# controller.net
KiCad netlist of a schematic drawn in EAGLE
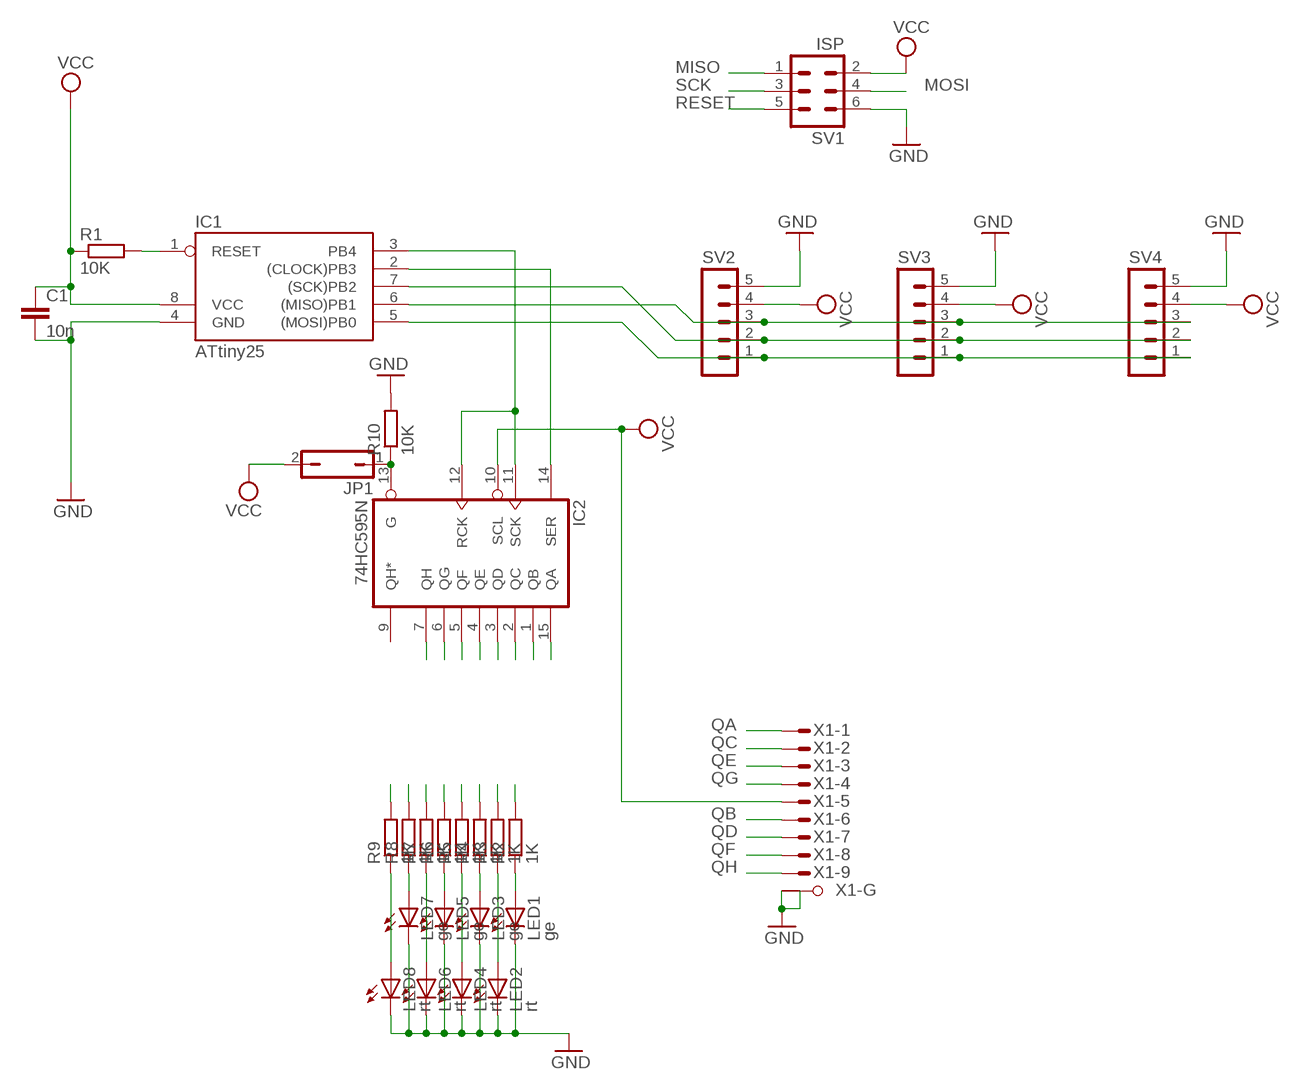
[diagram p0: schematic, sheet 1]

(export (version "E")
  (design (tool "Eeschema 10.0.6"))
  (components
    (comp (ref "C1")
      (value "10n")
      (footprint "eagle-import:C025-024X044")
      (libsource (lib "eagle-import") (part "C-EU025-024X044"))
    )
    (comp (ref "IC1")
      (value "ATtiny25")
      (footprint "eagle-import:DIL08")
      (libsource (lib "eagle-import") (part "AT902343PS"))
    )
    (comp (ref "IC2")
      (value "74HC595N")
      (footprint "eagle-import:DIL16")
      (libsource (lib "eagle-import") (part "74595NHC"))
    )
    (comp (ref "JP1")
      (value "JP1Q")
      (footprint "eagle-import:JP1")
      (libsource (lib "eagle-import") (part "JP1Q"))
    )
    (comp (ref "LED1")
      (value "ge")
      (footprint "eagle-import:LED5MM")
      (libsource (lib "eagle-import") (part "LED5MM"))
    )
    (comp (ref "LED2")
      (value "rt")
      (footprint "eagle-import:LED5MM")
      (libsource (lib "eagle-import") (part "LED5MM"))
    )
    (comp (ref "LED3")
      (value "ge")
      (footprint "eagle-import:LED5MM")
      (libsource (lib "eagle-import") (part "LED5MM"))
    )
    (comp (ref "LED4")
      (value "rt")
      (footprint "eagle-import:LED5MM")
      (libsource (lib "eagle-import") (part "LED5MM"))
    )
    (comp (ref "LED5")
      (value "ge")
      (footprint "eagle-import:LED5MM")
      (libsource (lib "eagle-import") (part "LED5MM"))
    )
    (comp (ref "LED6")
      (value "rt")
      (footprint "eagle-import:LED5MM")
      (libsource (lib "eagle-import") (part "LED5MM"))
    )
    (comp (ref "LED7")
      (value "ge")
      (footprint "eagle-import:LED5MM")
      (libsource (lib "eagle-import") (part "LED5MM"))
    )
    (comp (ref "LED8")
      (value "rt")
      (footprint "eagle-import:LED5MM")
      (libsource (lib "eagle-import") (part "LED5MM"))
    )
    (comp (ref "R1")
      (value "10K")
      (footprint "eagle-import:0207_7")
      (libsource (lib "eagle-import") (part "R-EU_0207/7"))
    )
    (comp (ref "R2")
      (value "1K")
      (footprint "eagle-import:0309_12")
      (libsource (lib "eagle-import") (part "R-EU_0309/12"))
    )
    (comp (ref "R3")
      (value "1K")
      (footprint "eagle-import:0309_12")
      (libsource (lib "eagle-import") (part "R-EU_0309/12"))
    )
    (comp (ref "R4")
      (value "1K")
      (footprint "eagle-import:0309_12")
      (libsource (lib "eagle-import") (part "R-EU_0309/12"))
    )
    (comp (ref "R5")
      (value "1K")
      (footprint "eagle-import:0309_12")
      (libsource (lib "eagle-import") (part "R-EU_0309/12"))
    )
    (comp (ref "R6")
      (value "1K")
      (footprint "eagle-import:0309_12")
      (libsource (lib "eagle-import") (part "R-EU_0309/12"))
    )
    (comp (ref "R7")
      (value "1K")
      (footprint "eagle-import:0309_12")
      (libsource (lib "eagle-import") (part "R-EU_0309/12"))
    )
    (comp (ref "R8")
      (value "1K")
      (footprint "eagle-import:0309_12")
      (libsource (lib "eagle-import") (part "R-EU_0309/12"))
    )
    (comp (ref "R9")
      (value "1K")
      (footprint "eagle-import:0309_12")
      (libsource (lib "eagle-import") (part "R-EU_0309/12"))
    )
    (comp (ref "R10")
      (value "10K")
      (footprint "eagle-import:0207_7")
      (libsource (lib "eagle-import") (part "R-EU_0207/7"))
    )
    (comp (ref "SV1")
      (value "ISP")
      (footprint "eagle-import:MA03-2")
      (libsource (lib "eagle-import") (part "MA03-2"))
    )
    (comp (ref "SV2")
      (value "MA05-1")
      (footprint "eagle-import:MA05-1")
      (libsource (lib "eagle-import") (part "MA05-1"))
    )
    (comp (ref "SV3")
      (value "MA05-1")
      (footprint "eagle-import:MA05-1")
      (libsource (lib "eagle-import") (part "MA05-1"))
    )
    (comp (ref "SV4")
      (value "MA05-1")
      (footprint "eagle-import:MA05-1")
      (libsource (lib "eagle-import") (part "MA05-1"))
    )
    (comp (ref "X1")
      (value "M09HPS")
      (footprint "eagle-import:M09HP")
      (libsource (lib "eagle-import") (part "M09HPS"))
    )
  )
  (nets
    (net (code "1") (name "/MISO") (class "Default")
      (node (ref "IC1") (pin "6") (pinfunction "(MISO)PB1_6") (pintype "bidirectional"))
      (node (ref "SV1") (pin "1") (pinfunction "1_1") (pintype "passive"))
      (node (ref "SV2") (pin "3") (pinfunction "3_3") (pintype "passive"))
      (node (ref "SV3") (pin "3") (pinfunction "3_3") (pintype "passive"))
      (node (ref "SV4") (pin "3") (pinfunction "3_3") (pintype "passive"))
    )
    (net (code "2") (name "/MOSI") (class "Default")
      (node (ref "IC1") (pin "5") (pinfunction "(MOSI)PB0_5") (pintype "bidirectional"))
      (node (ref "SV1") (pin "4") (pinfunction "4_4") (pintype "passive"))
      (node (ref "SV2") (pin "1") (pinfunction "1_1") (pintype "passive"))
      (node (ref "SV3") (pin "1") (pinfunction "1_1") (pintype "passive"))
      (node (ref "SV4") (pin "1") (pinfunction "1_1") (pintype "passive"))
    )
    (net (code "3") (name "/QA") (class "Default")
      (node (ref "IC2") (pin "15") (pinfunction "QA_15") (pintype "tri_state"))
      (node (ref "R2") (pin "2") (pinfunction "2_2") (pintype "passive"))
      (node (ref "X1") (pin "1") (pinfunction "M_1") (pintype "passive"))
    )
    (net (code "4") (name "/QB") (class "Default")
      (node (ref "IC2") (pin "1") (pinfunction "QB_1") (pintype "tri_state"))
      (node (ref "R6") (pin "2") (pinfunction "2_2") (pintype "passive"))
      (node (ref "X1") (pin "6") (pinfunction "M_6") (pintype "passive"))
    )
    (net (code "5") (name "/QC") (class "Default")
      (node (ref "IC2") (pin "2") (pinfunction "QC_2") (pintype "tri_state"))
      (node (ref "R3") (pin "2") (pinfunction "2_2") (pintype "passive"))
      (node (ref "X1") (pin "2") (pinfunction "M_2") (pintype "passive"))
    )
    (net (code "6") (name "/QD") (class "Default")
      (node (ref "IC2") (pin "3") (pinfunction "QD_3") (pintype "tri_state"))
      (node (ref "R7") (pin "2") (pinfunction "2_2") (pintype "passive"))
      (node (ref "X1") (pin "7") (pinfunction "M_7") (pintype "passive"))
    )
    (net (code "7") (name "/QE") (class "Default")
      (node (ref "IC2") (pin "4") (pinfunction "QE_4") (pintype "tri_state"))
      (node (ref "R4") (pin "2") (pinfunction "2_2") (pintype "passive"))
      (node (ref "X1") (pin "3") (pinfunction "M_3") (pintype "passive"))
    )
    (net (code "8") (name "/QF") (class "Default")
      (node (ref "IC2") (pin "5") (pinfunction "QF_5") (pintype "tri_state"))
      (node (ref "R8") (pin "2") (pinfunction "2_2") (pintype "passive"))
      (node (ref "X1") (pin "8") (pinfunction "M_8") (pintype "passive"))
    )
    (net (code "9") (name "/QG") (class "Default")
      (node (ref "IC2") (pin "6") (pinfunction "QG_6") (pintype "tri_state"))
      (node (ref "R5") (pin "2") (pinfunction "2_2") (pintype "passive"))
      (node (ref "X1") (pin "4") (pinfunction "M_4") (pintype "passive"))
    )
    (net (code "10") (name "/QH") (class "Default")
      (node (ref "IC2") (pin "7") (pinfunction "QH_7") (pintype "tri_state"))
      (node (ref "R9") (pin "2") (pinfunction "2_2") (pintype "passive"))
      (node (ref "X1") (pin "9") (pinfunction "M_9") (pintype "passive"))
    )
    (net (code "11") (name "/RESET") (class "Default")
      (node (ref "IC1") (pin "1") (pinfunction "RESET_1") (pintype "input"))
      (node (ref "R1") (pin "2") (pinfunction "2_2") (pintype "passive"))
      (node (ref "SV1") (pin "5") (pinfunction "5_5") (pintype "passive"))
    )
    (net (code "12") (name "/SCK") (class "Default")
      (node (ref "IC1") (pin "7") (pinfunction "(SCK)PB2_7") (pintype "bidirectional"))
      (node (ref "SV1") (pin "3") (pinfunction "3_3") (pintype "passive"))
      (node (ref "SV2") (pin "2") (pinfunction "2_2") (pintype "passive"))
      (node (ref "SV3") (pin "2") (pinfunction "2_2") (pintype "passive"))
      (node (ref "SV4") (pin "2") (pinfunction "2_2") (pintype "passive"))
    )
    (net (code "13") (name "GND") (class "Default")
      (node (ref "C1") (pin "2") (pinfunction "2_2") (pintype "passive"))
      (node (ref "IC1") (pin "4") (pinfunction "GND_4") (pintype "power_in"))
      (node (ref "LED1") (pin "K") (pinfunction "C_K") (pintype "passive"))
      (node (ref "LED2") (pin "K") (pinfunction "C_K") (pintype "passive"))
      (node (ref "LED3") (pin "K") (pinfunction "C_K") (pintype "passive"))
      (node (ref "LED4") (pin "K") (pinfunction "C_K") (pintype "passive"))
      (node (ref "LED5") (pin "K") (pinfunction "C_K") (pintype "passive"))
      (node (ref "LED6") (pin "K") (pinfunction "C_K") (pintype "passive"))
      (node (ref "LED7") (pin "K") (pinfunction "C_K") (pintype "passive"))
      (node (ref "LED8") (pin "K") (pinfunction "C_K") (pintype "passive"))
      (node (ref "R10") (pin "2") (pinfunction "2_2") (pintype "passive"))
      (node (ref "SV1") (pin "6") (pinfunction "6_6") (pintype "passive"))
      (node (ref "SV2") (pin "5") (pinfunction "5_5") (pintype "passive"))
      (node (ref "SV3") (pin "5") (pinfunction "5_5") (pintype "passive"))
      (node (ref "SV4") (pin "5") (pinfunction "5_5") (pintype "passive"))
      (node (ref "X1") (pin "G1") (pinfunction "G1_G1") (pintype "passive"))
      (node (ref "X1") (pin "G2") (pinfunction "G2_G2") (pintype "passive"))
    )
    (net (code "14") (name "Net-(IC1-(CLOCK)PB3)") (class "Default")
      (node (ref "IC1") (pin "2") (pinfunction "(CLOCK)PB3_2") (pintype "bidirectional"))
      (node (ref "IC2") (pin "14") (pinfunction "SER_14") (pintype "input"))
    )
    (net (code "15") (name "Net-(IC1-PB4)") (class "Default")
      (node (ref "IC1") (pin "3") (pinfunction "PB4_3") (pintype "bidirectional"))
      (node (ref "IC2") (pin "11") (pinfunction "SCK_11") (pintype "input"))
      (node (ref "IC2") (pin "12") (pinfunction "RCK_12") (pintype "input"))
    )
    (net (code "16") (name "Net-(IC2A-G)") (class "Default")
      (node (ref "IC2") (pin "13") (pinfunction "G_13") (pintype "input"))
      (node (ref "JP1") (pin "1") (pinfunction "1_1") (pintype "passive"))
      (node (ref "R10") (pin "1") (pinfunction "1_1") (pintype "passive"))
    )
    (net (code "17") (name "Net-(LED1-PadA)") (class "Default")
      (node (ref "LED1") (pin "A") (pinfunction "A_A") (pintype "passive"))
      (node (ref "R2") (pin "1") (pinfunction "1_1") (pintype "passive"))
    )
    (net (code "18") (name "Net-(LED2-PadA)") (class "Default")
      (node (ref "LED2") (pin "A") (pinfunction "A_A") (pintype "passive"))
      (node (ref "R3") (pin "1") (pinfunction "1_1") (pintype "passive"))
    )
    (net (code "19") (name "Net-(LED3-PadA)") (class "Default")
      (node (ref "LED3") (pin "A") (pinfunction "A_A") (pintype "passive"))
      (node (ref "R4") (pin "1") (pinfunction "1_1") (pintype "passive"))
    )
    (net (code "20") (name "Net-(LED4-PadA)") (class "Default")
      (node (ref "LED4") (pin "A") (pinfunction "A_A") (pintype "passive"))
      (node (ref "R5") (pin "1") (pinfunction "1_1") (pintype "passive"))
    )
    (net (code "21") (name "Net-(LED5-PadA)") (class "Default")
      (node (ref "LED5") (pin "A") (pinfunction "A_A") (pintype "passive"))
      (node (ref "R6") (pin "1") (pinfunction "1_1") (pintype "passive"))
    )
    (net (code "22") (name "Net-(LED6-PadA)") (class "Default")
      (node (ref "LED6") (pin "A") (pinfunction "A_A") (pintype "passive"))
      (node (ref "R7") (pin "1") (pinfunction "1_1") (pintype "passive"))
    )
    (net (code "23") (name "Net-(LED7-PadA)") (class "Default")
      (node (ref "LED7") (pin "A") (pinfunction "A_A") (pintype "passive"))
      (node (ref "R8") (pin "1") (pinfunction "1_1") (pintype "passive"))
    )
    (net (code "24") (name "Net-(LED8-PadA)") (class "Default")
      (node (ref "LED8") (pin "A") (pinfunction "A_A") (pintype "passive"))
      (node (ref "R9") (pin "1") (pinfunction "1_1") (pintype "passive"))
    )
    (net (code "25") (name "VCC") (class "Default")
      (node (ref "C1") (pin "1") (pinfunction "1_1") (pintype "passive"))
      (node (ref "IC1") (pin "8") (pinfunction "VCC_8") (pintype "power_in"))
      (node (ref "IC2") (pin "10") (pinfunction "SCL_10") (pintype "input"))
      (node (ref "JP1") (pin "2") (pinfunction "2_2") (pintype "passive"))
      (node (ref "R1") (pin "1") (pinfunction "1_1") (pintype "passive"))
      (node (ref "SV1") (pin "2") (pinfunction "2_2") (pintype "passive"))
      (node (ref "SV2") (pin "4") (pinfunction "4_4") (pintype "passive"))
      (node (ref "SV3") (pin "4") (pinfunction "4_4") (pintype "passive"))
      (node (ref "SV4") (pin "4") (pinfunction "4_4") (pintype "passive"))
      (node (ref "X1") (pin "5") (pinfunction "M_5") (pintype "passive"))
    )
    (net (code "26") (name "unconnected-(IC2A-QH*-Pad9)") (class "Default")
      (node (ref "IC2") (pin "9") (pinfunction "QH*_9") (pintype "tri_state"))
    )
  )
)
